# SDNL_DATN_RX_v1.net
KiCad netlist of a schematic drawn in Altium Designer
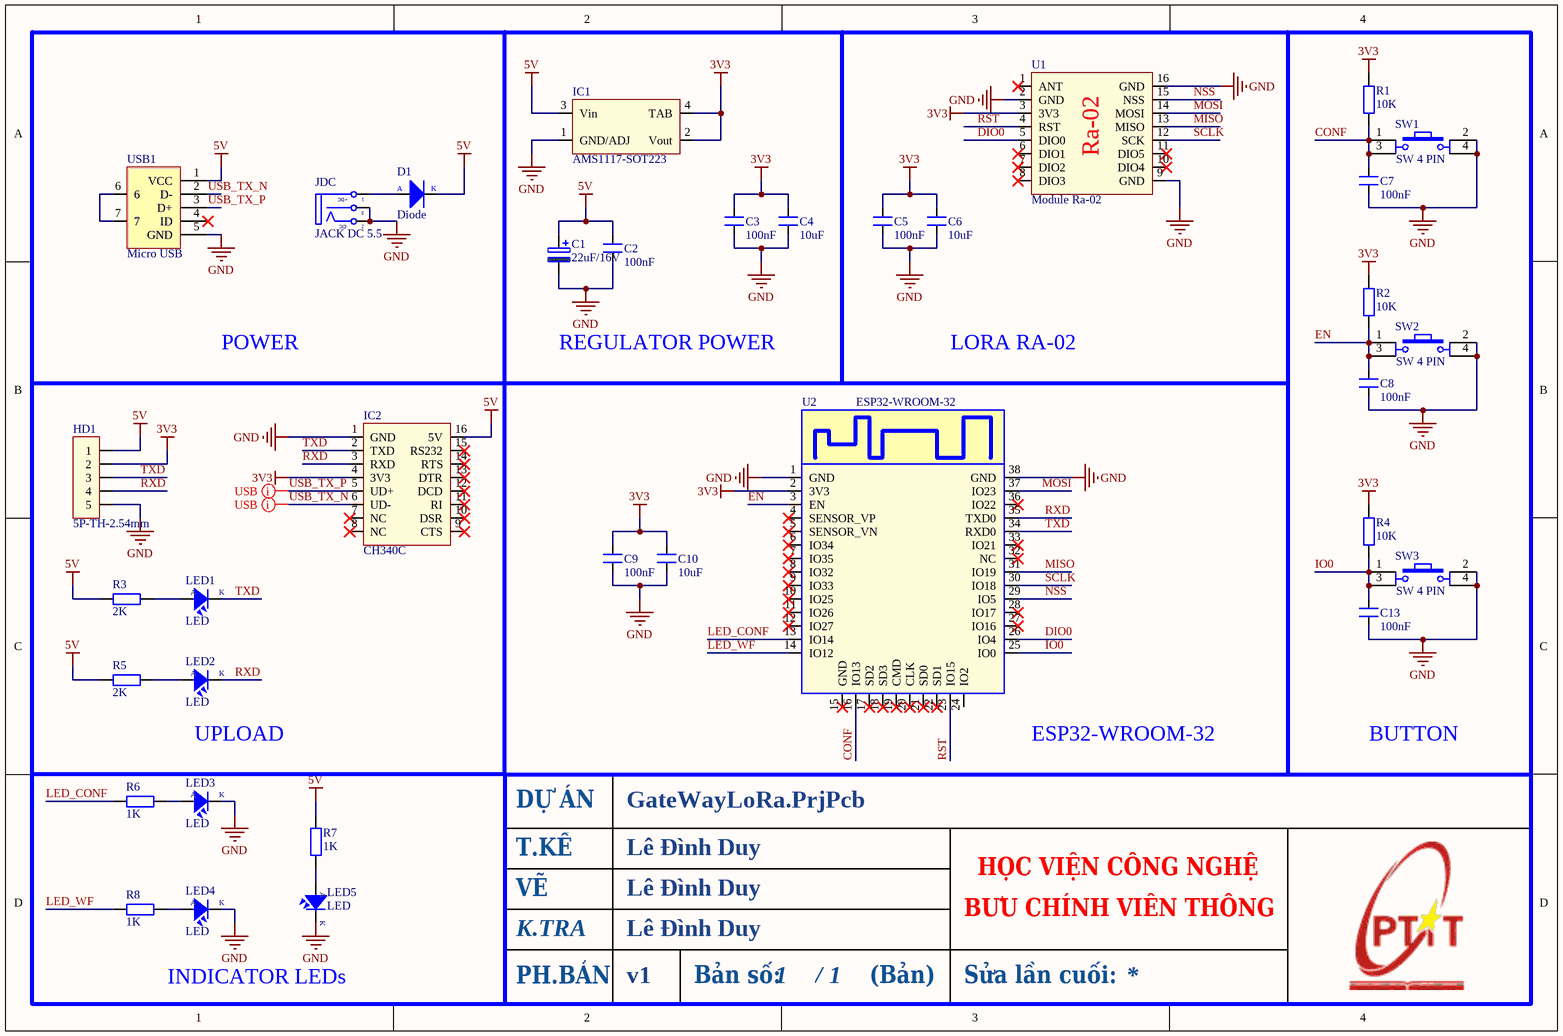
[diagram p0: SDNL_DATN_RX_v1.SchDoc]

(export (version "E")
  (design (tool "Eeschema 10.0.6"))
  (components
    (comp (ref "C1")
      (value "22uF/16V")
      (footprint "Cap Aluminum 4x5.4")
      (description "CAP ALUMINUM")
      (libsource (lib "ThanhTran_SchLib") (part "Capacitor Polarity"))
    )
    (comp (ref "C2")
      (value "100nF")
      (footprint "CAP SMD 0805")
      (description "CM 0805")
      (libsource (lib "PART") (part "CM"))
    )
    (comp (ref "C3")
      (value "100nF")
      (footprint "CAP SMD 0805")
      (description "CM 0805")
      (libsource (lib "PART") (part "CM"))
    )
    (comp (ref "C4")
      (value "10uF")
      (footprint "CAP SMD 0805")
      (description "Cap SMD")
      (libsource (lib "PART") (part "CM"))
    )
    (comp (ref "C5")
      (value "100nF")
      (footprint "CAP SMD 0805")
      (description "CM 0805")
      (libsource (lib "PART") (part "CM"))
    )
    (comp (ref "C6")
      (value "10uF")
      (footprint "CAP SMD 0805")
      (description "Cap SMD")
      (libsource (lib "PART") (part "CM"))
    )
    (comp (ref "C7")
      (value "100nF")
      (footprint "CAP SMD 0805")
      (description "CM 0805")
      (libsource (lib "PART") (part "CM"))
    )
    (comp (ref "C8")
      (value "100nF")
      (footprint "CAP SMD 0805")
      (description "CM 0805")
      (libsource (lib "PART") (part "CM"))
    )
    (comp (ref "C9")
      (value "100nF")
      (footprint "CAP SMD 0805")
      (description "CM 0805")
      (libsource (lib "PART") (part "CM"))
    )
    (comp (ref "C10")
      (value "10uF")
      (footprint "CAP SMD 0805")
      (description "Cap SMD")
      (libsource (lib "PART") (part "CM"))
    )
    (comp (ref "C13")
      (value "100nF")
      (footprint "CAP SMD 0805")
      (description "CM 0805")
      (libsource (lib "PART") (part "CM"))
    )
    (comp (ref "D1")
      (value "Diode")
      (footprint "DIODE SMA")
      (libsource (lib "ThanhTran_SchLib") (part "Diode"))
    )
    (comp (ref "HD1")
      (value "5P-TH-2.54mm")
      (footprint "XH2.54-5P")
      (libsource (lib "ThanhTran_SchLib") (part "Con5"))
    )
    (comp (ref "IC1")
      (value "AMS1117-SOT223")
      (footprint "AMS1117-SOT223")
      (libsource (lib "ThanhTran_SchLib") (part "AMS1117"))
    )
    (comp (ref "IC2")
      (value "CH340C")
      (footprint "SOP-16")
      (libsource (lib "ThanhTran_SchLib") (part "CH340C"))
    )
    (comp (ref "JDC")
      (value "JACK DC 5.5")
      (footprint "DC IN")
      (libsource (lib "ThanhTran_SchLib") (part "DC IN 5.5"))
    )
    (comp (ref "LED1")
      (value "LED")
      (footprint "LED SMD 0805")
      (description "LED Single colour Green and Red")
      (libsource (lib "PART") (part "LED"))
    )
    (comp (ref "LED2")
      (value "LED")
      (footprint "LED SMD 0805")
      (description "LED Single colour Green and Red")
      (libsource (lib "PART") (part "LED"))
    )
    (comp (ref "LED3")
      (value "LED")
      (footprint "LED SMD 0805")
      (description "LED Single colour Green and Red")
      (libsource (lib "PART") (part "LED"))
    )
    (comp (ref "LED4")
      (value "LED")
      (footprint "LED SMD 0805")
      (description "LED Single colour Green and Red")
      (libsource (lib "PART") (part "LED"))
    )
    (comp (ref "LED5")
      (value "LED")
      (footprint "LED SMD 0805")
      (description "LED Single colour Green and Red")
      (libsource (lib "PART") (part "LED"))
    )
    (comp (ref "R1")
      (value "10K")
      (footprint "RES SMD 0805")
      (description "Resistor SMD")
      (libsource (lib "PART") (part "RM"))
    )
    (comp (ref "R2")
      (value "10K")
      (footprint "RES SMD 0805")
      (description "Resistor SMD")
      (libsource (lib "PART") (part "RM"))
    )
    (comp (ref "R3")
      (value "2K")
      (footprint "RES SMD 0805")
      (description "Resistor SMD")
      (libsource (lib "PART") (part "RM"))
    )
    (comp (ref "R4")
      (value "10K")
      (footprint "RES SMD 0805")
      (description "Resistor SMD")
      (libsource (lib "PART") (part "RM"))
    )
    (comp (ref "R5")
      (value "2K")
      (footprint "RES SMD 0805")
      (description "Resistor SMD")
      (libsource (lib "PART") (part "RM"))
    )
    (comp (ref "R6")
      (value "1K")
      (footprint "RES SMD 0805")
      (description "Resistor SMD")
      (libsource (lib "PART") (part "RM"))
    )
    (comp (ref "R7")
      (value "1K")
      (footprint "RES SMD 0805")
      (description "Resistor SMD")
      (libsource (lib "PART") (part "RM"))
    )
    (comp (ref "R8")
      (value "1K")
      (footprint "RES SMD 0805")
      (description "Resistor SMD")
      (libsource (lib "PART") (part "RM"))
    )
    (comp (ref "SW1")
      (value "SW 4 PIN")
      (footprint "SW 4 PIN TH")
      (libsource (lib "ThanhTran_SchLib") (part "SW 4 PIN"))
    )
    (comp (ref "SW2")
      (value "SW 4 PIN")
      (footprint "SW 4 PIN TH")
      (libsource (lib "ThanhTran_SchLib") (part "SW 4 PIN"))
    )
    (comp (ref "SW3")
      (value "SW 4 PIN")
      (footprint "SW 4 PIN TH")
      (libsource (lib "ThanhTran_SchLib") (part "SW 4 PIN"))
    )
    (comp (ref "U1")
      (value "Module Ra-02")
      (footprint "module ra02")
      (libsource (lib "ThanhTran_SchLib") (part "Module Ra02"))
    )
    (comp (ref "U2")
      (value "ESP32-WROOM-32")
      (footprint "ESP32-WROOM-32")
      (libsource (lib "ThanhTran_SchLib") (part "ESP32-WROOM-32"))
    )
    (comp (ref "USB1")
      (value "Micro USB")
      (footprint "MICRO USB CONNECTOR")
      (libsource (lib "ThanhTran_SchLib") (part "Micro USB Connector"))
    )
  )
  (nets
    (net (code "1") (name "/CONF") (class "Default")
      (node (ref "C7") (pin "2") (pinfunction "2_2") (pintype "passive"))
      (node (ref "R1") (pin "1") (pinfunction "1_1") (pintype "passive"))
      (node (ref "SW1") (pin "1") (pintype "passive"))
      (node (ref "SW1") (pin "3") (pintype "passive"))
      (node (ref "U2") (pin "16") (pinfunction "IO13_16") (pintype "passive"))
    )
    (net (code "2") (name "/DIO0") (class "Default")
      (node (ref "U1") (pin "5") (pinfunction "DIO0_5") (pintype "passive"))
      (node (ref "U2") (pin "26") (pinfunction "IO4_26") (pintype "passive"))
    )
    (net (code "3") (name "/EN") (class "Default")
      (node (ref "C8") (pin "2") (pinfunction "2_2") (pintype "passive"))
      (node (ref "R2") (pin "1") (pinfunction "1_1") (pintype "passive"))
      (node (ref "SW2") (pin "1") (pintype "passive"))
      (node (ref "SW2") (pin "3") (pintype "passive"))
      (node (ref "U2") (pin "3") (pinfunction "EN_3") (pintype "passive"))
    )
    (net (code "4") (name "/IO0") (class "Default")
      (node (ref "C13") (pin "2") (pinfunction "2_2") (pintype "passive"))
      (node (ref "R4") (pin "1") (pinfunction "1_1") (pintype "passive"))
      (node (ref "SW3") (pin "1") (pintype "passive"))
      (node (ref "SW3") (pin "3") (pintype "passive"))
      (node (ref "U2") (pin "25") (pinfunction "IO0_25") (pintype "passive"))
    )
    (net (code "5") (name "/LED_CONF") (class "Default")
      (node (ref "R6") (pin "1") (pinfunction "1_1") (pintype "passive"))
      (node (ref "U2") (pin "13") (pinfunction "IO14_13") (pintype "passive"))
    )
    (net (code "6") (name "/LED_WF") (class "Default")
      (node (ref "R8") (pin "1") (pinfunction "1_1") (pintype "passive"))
      (node (ref "U2") (pin "14") (pinfunction "IO12_14") (pintype "passive"))
    )
    (net (code "7") (name "/MISO") (class "Default")
      (node (ref "U1") (pin "13") (pinfunction "MISO_13") (pintype "passive"))
      (node (ref "U2") (pin "31") (pinfunction "IO19_31") (pintype "passive"))
    )
    (net (code "8") (name "/MOSI") (class "Default")
      (node (ref "U1") (pin "14") (pinfunction "MOSI_14") (pintype "passive"))
      (node (ref "U2") (pin "37") (pinfunction "IO23_37") (pintype "passive"))
    )
    (net (code "9") (name "/NSS") (class "Default")
      (node (ref "U1") (pin "15") (pinfunction "NSS_15") (pintype "passive"))
      (node (ref "U2") (pin "29") (pinfunction "IO5_29") (pintype "passive"))
    )
    (net (code "10") (name "/RST") (class "Default")
      (node (ref "U1") (pin "4") (pinfunction "RST_4") (pintype "passive"))
      (node (ref "U2") (pin "23") (pinfunction "IO15_23") (pintype "passive"))
    )
    (net (code "11") (name "/RXD") (class "Default")
      (node (ref "HD1") (pin "4") (pinfunction "4_4") (pintype "passive"))
      (node (ref "IC2") (pin "3") (pinfunction "RXD_3") (pintype "passive"))
      (node (ref "LED2") (pin "2") (pinfunction "K_2") (pintype "passive"))
      (node (ref "U2") (pin "35") (pinfunction "TXD0_35") (pintype "passive"))
    )
    (net (code "12") (name "/SCLK") (class "Default")
      (node (ref "U1") (pin "12") (pinfunction "SCK_12") (pintype "passive"))
      (node (ref "U2") (pin "30") (pinfunction "IO18_30") (pintype "passive"))
    )
    (net (code "13") (name "/TXD") (class "Default")
      (node (ref "HD1") (pin "3") (pinfunction "3_3") (pintype "passive"))
      (node (ref "IC2") (pin "2") (pinfunction "TXD_2") (pintype "passive"))
      (node (ref "LED1") (pin "2") (pinfunction "K_2") (pintype "passive"))
      (node (ref "U2") (pin "34") (pinfunction "RXD0_34") (pintype "passive"))
    )
    (net (code "14") (name "/USB_TX_N") (class "Default")
      (node (ref "IC2") (pin "6") (pinfunction "UD-_6") (pintype "passive"))
      (node (ref "USB1") (pin "2") (pinfunction "D-_2") (pintype "passive"))
    )
    (net (code "15") (name "/USB_TX_P") (class "Default")
      (node (ref "IC2") (pin "5") (pinfunction "UD+_5") (pintype "passive"))
      (node (ref "USB1") (pin "3") (pinfunction "D+_3") (pintype "passive"))
    )
    (net (code "16") (name "3V3") (class "Default")
      (node (ref "C10") (pin "2") (pinfunction "2_2") (pintype "passive"))
      (node (ref "C3") (pin "2") (pinfunction "2_2") (pintype "passive"))
      (node (ref "C4") (pin "2") (pinfunction "2_2") (pintype "passive"))
      (node (ref "C5") (pin "2") (pinfunction "2_2") (pintype "passive"))
      (node (ref "C6") (pin "2") (pinfunction "2_2") (pintype "passive"))
      (node (ref "C9") (pin "2") (pinfunction "2_2") (pintype "passive"))
      (node (ref "HD1") (pin "2") (pinfunction "2_2") (pintype "passive"))
      (node (ref "IC1") (pin "2") (pinfunction "Vout_2") (pintype "passive"))
      (node (ref "IC1") (pin "4") (pinfunction "TAB_4") (pintype "passive"))
      (node (ref "IC2") (pin "4") (pinfunction "3V3_4") (pintype "passive"))
      (node (ref "R1") (pin "2") (pinfunction "2_2") (pintype "passive"))
      (node (ref "R2") (pin "2") (pinfunction "2_2") (pintype "passive"))
      (node (ref "R4") (pin "2") (pinfunction "2_2") (pintype "passive"))
      (node (ref "U1") (pin "3") (pinfunction "3V3_3") (pintype "passive"))
      (node (ref "U2") (pin "2") (pinfunction "3V3_2") (pintype "passive"))
    )
    (net (code "17") (name "5V") (class "Default")
      (node (ref "C1") (pin "1") (pinfunction "1_1") (pintype "passive"))
      (node (ref "C2") (pin "2") (pinfunction "2_2") (pintype "passive"))
      (node (ref "D1") (pin "2") (pinfunction "K_2") (pintype "passive"))
      (node (ref "HD1") (pin "1") (pinfunction "1_1") (pintype "passive"))
      (node (ref "IC1") (pin "3") (pinfunction "Vin_3") (pintype "passive"))
      (node (ref "IC2") (pin "16") (pinfunction "5V_16") (pintype "passive"))
      (node (ref "R3") (pin "2") (pinfunction "2_2") (pintype "passive"))
      (node (ref "R5") (pin "2") (pinfunction "2_2") (pintype "passive"))
      (node (ref "R7") (pin "1") (pinfunction "1_1") (pintype "passive"))
      (node (ref "USB1") (pin "1") (pinfunction "VCC_1") (pintype "passive"))
    )
    (net (code "18") (name "GND") (class "Default")
      (node (ref "C1") (pin "2") (pinfunction "2_2") (pintype "passive"))
      (node (ref "C10") (pin "1") (pinfunction "1_1") (pintype "passive"))
      (node (ref "C13") (pin "1") (pinfunction "1_1") (pintype "passive"))
      (node (ref "C2") (pin "1") (pinfunction "1_1") (pintype "passive"))
      (node (ref "C3") (pin "1") (pinfunction "1_1") (pintype "passive"))
      (node (ref "C4") (pin "1") (pinfunction "1_1") (pintype "passive"))
      (node (ref "C5") (pin "1") (pinfunction "1_1") (pintype "passive"))
      (node (ref "C6") (pin "1") (pinfunction "1_1") (pintype "passive"))
      (node (ref "C7") (pin "1") (pinfunction "1_1") (pintype "passive"))
      (node (ref "C8") (pin "1") (pinfunction "1_1") (pintype "passive"))
      (node (ref "C9") (pin "1") (pinfunction "1_1") (pintype "passive"))
      (node (ref "HD1") (pin "5") (pinfunction "5_5") (pintype "passive"))
      (node (ref "IC1") (pin "1") (pinfunction "GND/ADJ_1") (pintype "passive"))
      (node (ref "IC2") (pin "1") (pinfunction "GND_1") (pintype "passive"))
      (node (ref "JDC") (pin "2") (pinfunction "TN_2") (pintype "passive"))
      (node (ref "JDC") (pin "3") (pinfunction "S_3") (pintype "power_in"))
      (node (ref "LED3") (pin "2") (pinfunction "K_2") (pintype "passive"))
      (node (ref "LED4") (pin "2") (pinfunction "K_2") (pintype "passive"))
      (node (ref "LED5") (pin "2") (pinfunction "K_2") (pintype "passive"))
      (node (ref "SW1") (pin "2") (pintype "passive"))
      (node (ref "SW1") (pin "4") (pintype "passive"))
      (node (ref "SW2") (pin "2") (pintype "passive"))
      (node (ref "SW2") (pin "4") (pintype "passive"))
      (node (ref "SW3") (pin "2") (pintype "passive"))
      (node (ref "SW3") (pin "4") (pintype "passive"))
      (node (ref "U1") (pin "16") (pinfunction "GND_16") (pintype "passive"))
      (node (ref "U1") (pin "2") (pinfunction "GND_2") (pintype "passive"))
      (node (ref "U1") (pin "9") (pinfunction "GND_9") (pintype "passive"))
      (node (ref "U2") (pin "1") (pinfunction "GND_1") (pintype "passive"))
      (node (ref "U2") (pin "38") (pinfunction "GND_38") (pintype "passive"))
      (node (ref "USB1") (pin "5") (pinfunction "GND_5") (pintype "passive"))
    )
    (net (code "19") (name "Net-(D1-A)") (class "Default")
      (node (ref "D1") (pin "1") (pinfunction "A_1") (pintype "passive"))
      (node (ref "JDC") (pin "1") (pinfunction "T_1") (pintype "passive"))
    )
    (net (code "20") (name "Net-(LED1-A)") (class "Default")
      (node (ref "LED1") (pin "1") (pinfunction "A_1") (pintype "passive"))
      (node (ref "R3") (pin "1") (pinfunction "1_1") (pintype "passive"))
    )
    (net (code "21") (name "Net-(LED2-A)") (class "Default")
      (node (ref "LED2") (pin "1") (pinfunction "A_1") (pintype "passive"))
      (node (ref "R5") (pin "1") (pinfunction "1_1") (pintype "passive"))
    )
    (net (code "22") (name "Net-(LED3-A)") (class "Default")
      (node (ref "LED3") (pin "1") (pinfunction "A_1") (pintype "passive"))
      (node (ref "R6") (pin "2") (pinfunction "2_2") (pintype "passive"))
    )
    (net (code "23") (name "Net-(LED4-A)") (class "Default")
      (node (ref "LED4") (pin "1") (pinfunction "A_1") (pintype "passive"))
      (node (ref "R8") (pin "2") (pinfunction "2_2") (pintype "passive"))
    )
    (net (code "24") (name "Net-(LED5-A)") (class "Default")
      (node (ref "LED5") (pin "1") (pinfunction "A_1") (pintype "passive"))
      (node (ref "R7") (pin "2") (pinfunction "2_2") (pintype "passive"))
    )
    (net (code "25") (name "Net-(USB1-Pad6)") (class "Default")
      (node (ref "USB1") (pin "6") (pinfunction "6_6") (pintype "passive"))
      (node (ref "USB1") (pin "7") (pinfunction "7_7") (pintype "passive"))
    )
    (net (code "26") (name "unconnected-(IC2-CTS-Pad9)") (class "Default")
      (node (ref "IC2") (pin "9") (pinfunction "CTS_9") (pintype "passive+no_connect"))
    )
    (net (code "27") (name "unconnected-(IC2-DCD-Pad12)") (class "Default")
      (node (ref "IC2") (pin "12") (pinfunction "DCD_12") (pintype "passive+no_connect"))
    )
    (net (code "28") (name "unconnected-(IC2-DSR-Pad10)") (class "Default")
      (node (ref "IC2") (pin "10") (pinfunction "DSR_10") (pintype "passive+no_connect"))
    )
    (net (code "29") (name "unconnected-(IC2-DTR-Pad13)") (class "Default")
      (node (ref "IC2") (pin "13") (pinfunction "DTR_13") (pintype "passive+no_connect"))
    )
    (net (code "30") (name "unconnected-(IC2-NC-Pad7)") (class "Default")
      (node (ref "IC2") (pin "7") (pinfunction "NC_7") (pintype "passive+no_connect"))
    )
    (net (code "31") (name "unconnected-(IC2-NC-Pad8)") (class "Default")
      (node (ref "IC2") (pin "8") (pinfunction "NC_8") (pintype "passive+no_connect"))
    )
    (net (code "32") (name "unconnected-(IC2-RI-Pad11)") (class "Default")
      (node (ref "IC2") (pin "11") (pinfunction "RI_11") (pintype "passive+no_connect"))
    )
    (net (code "33") (name "unconnected-(IC2-RS232-Pad15)") (class "Default")
      (node (ref "IC2") (pin "15") (pinfunction "RS232_15") (pintype "passive+no_connect"))
    )
    (net (code "34") (name "unconnected-(IC2-RTS-Pad14)") (class "Default")
      (node (ref "IC2") (pin "14") (pinfunction "RTS_14") (pintype "passive+no_connect"))
    )
    (net (code "35") (name "unconnected-(U1-ANT-Pad1)") (class "Default")
      (node (ref "U1") (pin "1") (pinfunction "ANT_1") (pintype "passive+no_connect"))
    )
    (net (code "36") (name "unconnected-(U1-DIO1-Pad6)") (class "Default")
      (node (ref "U1") (pin "6") (pinfunction "DIO1_6") (pintype "passive+no_connect"))
    )
    (net (code "37") (name "unconnected-(U1-DIO2-Pad7)") (class "Default")
      (node (ref "U1") (pin "7") (pinfunction "DIO2_7") (pintype "passive+no_connect"))
    )
    (net (code "38") (name "unconnected-(U1-DIO3-Pad8)") (class "Default")
      (node (ref "U1") (pin "8") (pinfunction "DIO3_8") (pintype "passive+no_connect"))
    )
    (net (code "39") (name "unconnected-(U1-DIO4-Pad10)") (class "Default")
      (node (ref "U1") (pin "10") (pinfunction "DIO4_10") (pintype "passive+no_connect"))
    )
    (net (code "40") (name "unconnected-(U1-DIO5-Pad11)") (class "Default")
      (node (ref "U1") (pin "11") (pinfunction "DIO5_11") (pintype "passive+no_connect"))
    )
    (net (code "41") (name "unconnected-(U2-CLK-Pad20)") (class "Default")
      (node (ref "U2") (pin "20") (pinfunction "CLK_20") (pintype "passive+no_connect"))
    )
    (net (code "42") (name "unconnected-(U2-CMD-Pad19)") (class "Default")
      (node (ref "U2") (pin "19") (pinfunction "CMD_19") (pintype "passive+no_connect"))
    )
    (net (code "43") (name "unconnected-(U2-GND-Pad15)") (class "Default")
      (node (ref "U2") (pin "15") (pinfunction "GND_15") (pintype "passive+no_connect"))
    )
    (net (code "44") (name "unconnected-(U2-IO2-Pad24)") (class "Default")
      (node (ref "U2") (pin "24") (pinfunction "IO2_24") (pintype "passive"))
    )
    (net (code "45") (name "unconnected-(U2-IO16-Pad27)") (class "Default")
      (node (ref "U2") (pin "27") (pinfunction "IO16_27") (pintype "passive+no_connect"))
    )
    (net (code "46") (name "unconnected-(U2-IO17-Pad28)") (class "Default")
      (node (ref "U2") (pin "28") (pinfunction "IO17_28") (pintype "passive+no_connect"))
    )
    (net (code "47") (name "unconnected-(U2-IO21-Pad33)") (class "Default")
      (node (ref "U2") (pin "33") (pinfunction "IO21_33") (pintype "passive+no_connect"))
    )
    (net (code "48") (name "unconnected-(U2-IO22-Pad36)") (class "Default")
      (node (ref "U2") (pin "36") (pinfunction "IO22_36") (pintype "passive+no_connect"))
    )
    (net (code "49") (name "unconnected-(U2-IO25-Pad10)") (class "Default")
      (node (ref "U2") (pin "10") (pinfunction "IO25_10") (pintype "passive+no_connect"))
    )
    (net (code "50") (name "unconnected-(U2-IO26-Pad11)") (class "Default")
      (node (ref "U2") (pin "11") (pinfunction "IO26_11") (pintype "passive+no_connect"))
    )
    (net (code "51") (name "unconnected-(U2-IO27-Pad12)") (class "Default")
      (node (ref "U2") (pin "12") (pinfunction "IO27_12") (pintype "passive+no_connect"))
    )
    (net (code "52") (name "unconnected-(U2-IO32-Pad8)") (class "Default")
      (node (ref "U2") (pin "8") (pinfunction "IO32_8") (pintype "passive+no_connect"))
    )
    (net (code "53") (name "unconnected-(U2-IO33-Pad9)") (class "Default")
      (node (ref "U2") (pin "9") (pinfunction "IO33_9") (pintype "passive+no_connect"))
    )
    (net (code "54") (name "unconnected-(U2-IO34-Pad6)") (class "Default")
      (node (ref "U2") (pin "6") (pinfunction "IO34_6") (pintype "passive+no_connect"))
    )
    (net (code "55") (name "unconnected-(U2-IO35-Pad7)") (class "Default")
      (node (ref "U2") (pin "7") (pinfunction "IO35_7") (pintype "passive+no_connect"))
    )
    (net (code "56") (name "unconnected-(U2-NC-Pad32)") (class "Default")
      (node (ref "U2") (pin "32") (pinfunction "NC_32") (pintype "passive+no_connect"))
    )
    (net (code "57") (name "unconnected-(U2-SD0-Pad21)") (class "Default")
      (node (ref "U2") (pin "21") (pinfunction "SD0_21") (pintype "passive+no_connect"))
    )
    (net (code "58") (name "unconnected-(U2-SD1-Pad22)") (class "Default")
      (node (ref "U2") (pin "22") (pinfunction "SD1_22") (pintype "passive+no_connect"))
    )
    (net (code "59") (name "unconnected-(U2-SD2-Pad17)") (class "Default")
      (node (ref "U2") (pin "17") (pinfunction "SD2_17") (pintype "passive+no_connect"))
    )
    (net (code "60") (name "unconnected-(U2-SD3-Pad18)") (class "Default")
      (node (ref "U2") (pin "18") (pinfunction "SD3_18") (pintype "passive+no_connect"))
    )
    (net (code "61") (name "unconnected-(U2-SENSOR_VN-Pad5)") (class "Default")
      (node (ref "U2") (pin "5") (pinfunction "SENSOR_VN_5") (pintype "passive+no_connect"))
    )
    (net (code "62") (name "unconnected-(U2-SENSOR_VP-Pad4)") (class "Default")
      (node (ref "U2") (pin "4") (pinfunction "SENSOR_VP_4") (pintype "passive+no_connect"))
    )
    (net (code "63") (name "unconnected-(USB1-ID-Pad4)") (class "Default")
      (node (ref "USB1") (pin "4") (pinfunction "ID_4") (pintype "passive+no_connect"))
    )
  )
)
